# LB_BIT_1IN_3OUT-XL-v03_1_1x.net
KiCad netlist of a schematic drawn in EAGLE
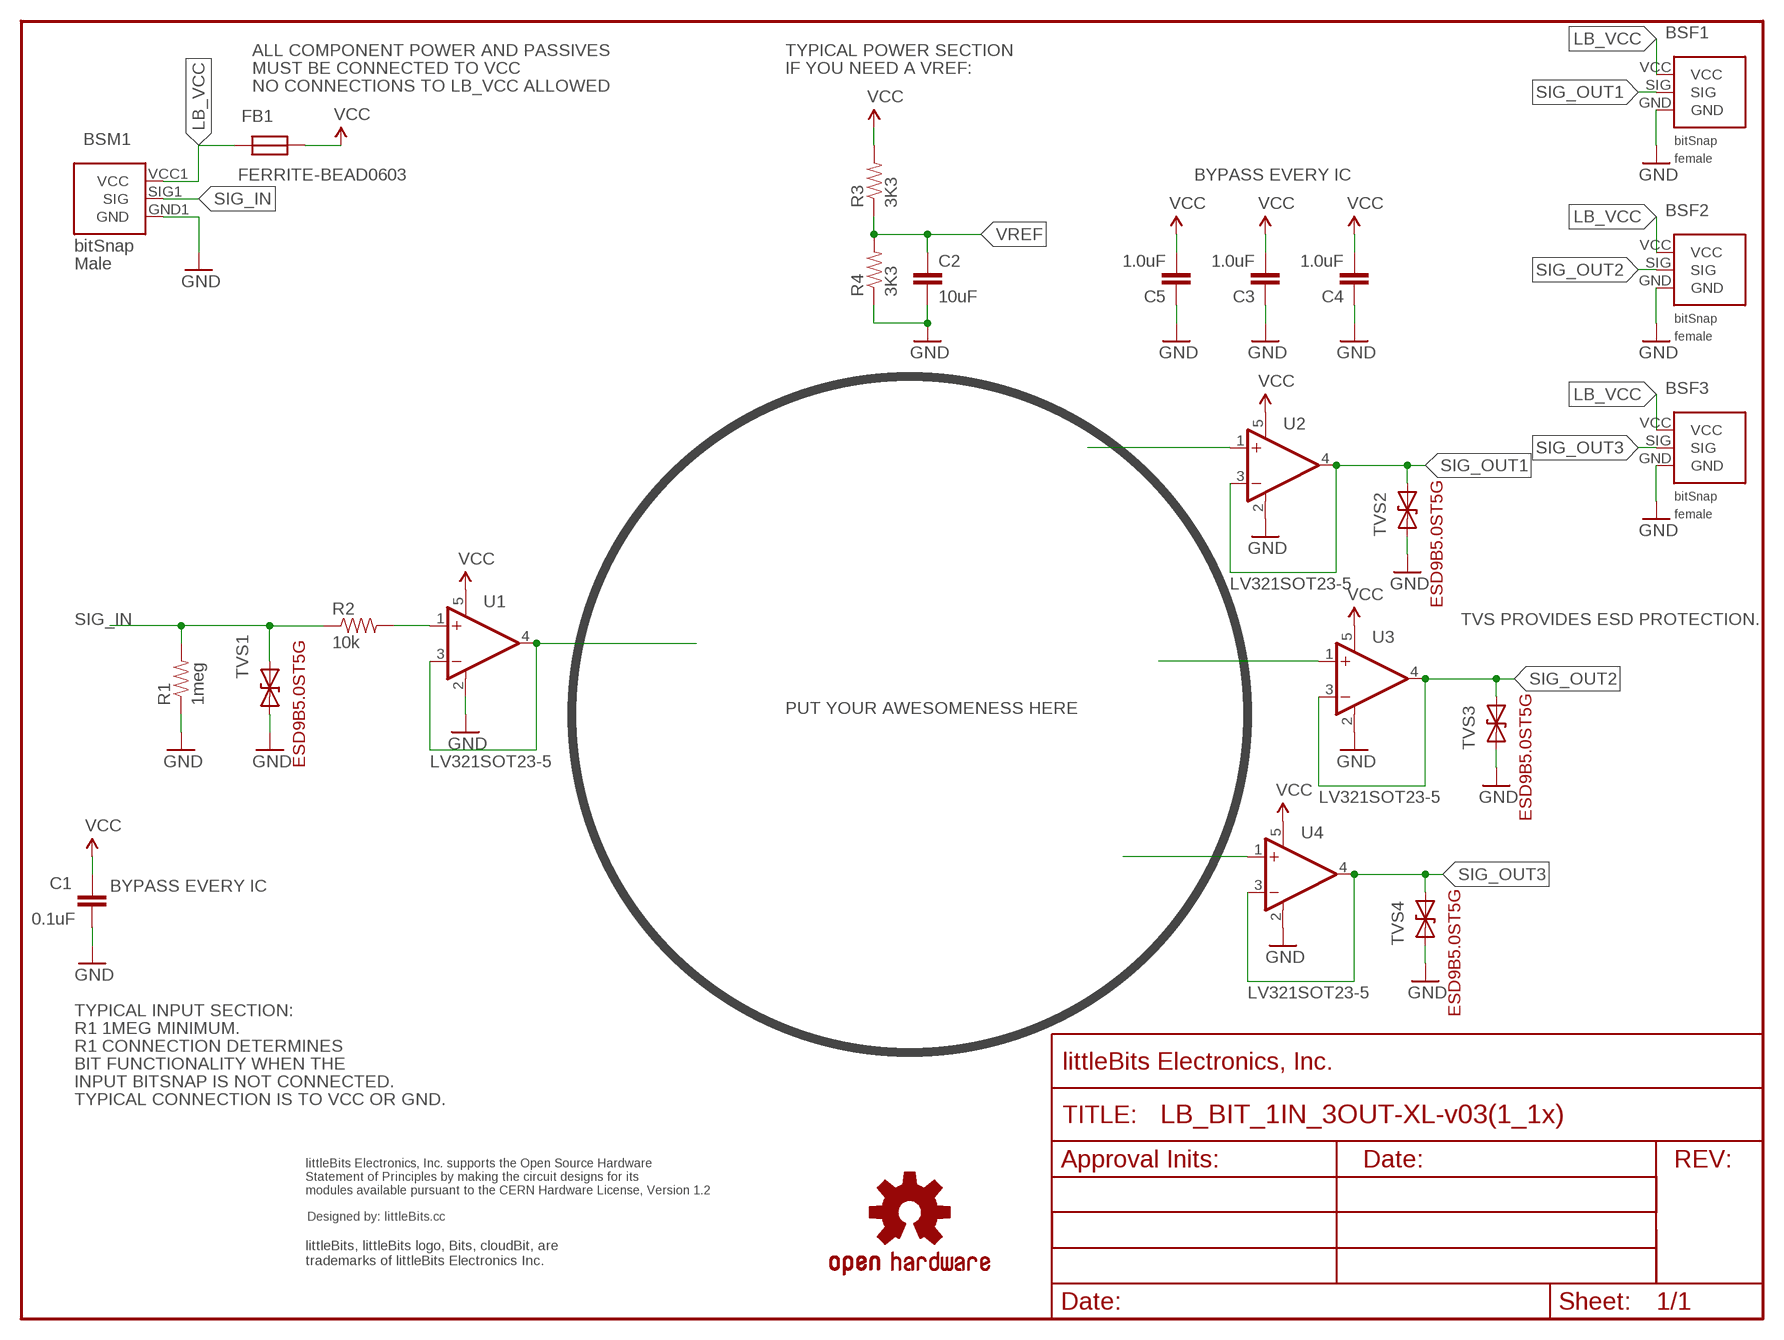
[diagram p0: schematic, sheet 1]

(export (version "E")
  (design (tool "Eeschema 10.0.6"))
  (components
    (comp (ref "BSF1")
      (value "BITSNAP_V03_FEMALE")
      (footprint "eagle-import:BITSNAP_V03_FEMALE")
      (libsource (lib "eagle-import") (part "BITSNAP_V03_FEMALE"))
    )
    (comp (ref "BSF2")
      (value "BITSNAP_V03_FEMALE")
      (footprint "eagle-import:BITSNAP_V03_FEMALE")
      (libsource (lib "eagle-import") (part "BITSNAP_V03_FEMALE"))
    )
    (comp (ref "BSF3")
      (value "BITSNAP_V03_FEMALE")
      (footprint "eagle-import:BITSNAP_V03_FEMALE")
      (libsource (lib "eagle-import") (part "BITSNAP_V03_FEMALE"))
    )
    (comp (ref "BSM1")
      (value "BITSNAP_V03_MALE")
      (footprint "eagle-import:BITSNAP_V03_MALE")
      (libsource (lib "eagle-import") (part "BITSNAP_V03_MALE"))
    )
    (comp (ref "C1")
      (value "0.1uF")
      (footprint "eagle-import:CAP-0603")
      (libsource (lib "eagle-import") (part "CAPCAP-0603"))
    )
    (comp (ref "C2")
      (value "10uF")
      (footprint "eagle-import:CAP-0603")
      (libsource (lib "eagle-import") (part "CAPCAP-0603"))
    )
    (comp (ref "C3")
      (value "1.0uF")
      (footprint "eagle-import:CAP-0603")
      (libsource (lib "eagle-import") (part "CAPCAP-0603"))
    )
    (comp (ref "C4")
      (value "1.0uF")
      (footprint "eagle-import:CAP-0603")
      (libsource (lib "eagle-import") (part "CAPCAP-0603"))
    )
    (comp (ref "C5")
      (value "1.0uF")
      (footprint "eagle-import:CAP-0603")
      (libsource (lib "eagle-import") (part "CAPCAP-0603"))
    )
    (comp (ref "FB1")
      (value "FERRITE-BEAD0603")
      (footprint "eagle-import:R0603")
      (libsource (lib "eagle-import") (part "FERRITE-BEAD0603"))
    )
    (comp (ref "FRAME1")
      (value "FRAME-LETTER")
      (footprint "eagle-import:FABDWG01-OHW")
      (libsource (lib "eagle-import") (part "FRAME-LETTER"))
    )
    (comp (ref "R1")
      (value "1meg")
      (footprint "eagle-import:RES-0603")
      (libsource (lib "eagle-import") (part "RESISTOR0603"))
    )
    (comp (ref "R2")
      (value "10k")
      (footprint "eagle-import:RES-0603")
      (libsource (lib "eagle-import") (part "RESISTOR0603"))
    )
    (comp (ref "R3")
      (value "3K3")
      (footprint "eagle-import:RES-0603")
      (libsource (lib "eagle-import") (part "RESISTOR0603"))
    )
    (comp (ref "R4")
      (value "3K3")
      (footprint "eagle-import:RES-0603")
      (libsource (lib "eagle-import") (part "RESISTOR0603"))
    )
    (comp (ref "TVS1")
      (value "DIODE-TVSSOD-923")
      (footprint "eagle-import:SOD-923")
      (fields (field (name "MPN") "ESD9B5.0ST5G"))
      (libsource (lib "eagle-import") (part "DIODE-TVSSOD-923"))
    )
    (comp (ref "TVS2")
      (value "DIODE-TVSSOD-923")
      (footprint "eagle-import:SOD-923")
      (fields (field (name "MPN") "ESD9B5.0ST5G"))
      (libsource (lib "eagle-import") (part "DIODE-TVSSOD-923"))
    )
    (comp (ref "TVS3")
      (value "DIODE-TVSSOD-923")
      (footprint "eagle-import:SOD-923")
      (fields (field (name "MPN") "ESD9B5.0ST5G"))
      (libsource (lib "eagle-import") (part "DIODE-TVSSOD-923"))
    )
    (comp (ref "TVS4")
      (value "DIODE-TVSSOD-923")
      (footprint "eagle-import:SOD-923")
      (fields (field (name "MPN") "ESD9B5.0ST5G"))
      (libsource (lib "eagle-import") (part "DIODE-TVSSOD-923"))
    )
    (comp (ref "U$1")
      (value "OSHWCREDIT")
      (footprint "eagle-import:OSHWCREDIT")
      (libsource (lib "eagle-import") (part "OSHWCREDIT"))
    )
    (comp (ref "U$6")
      (value "OSHW-LOGOL")
      (footprint "eagle-import:OSHW-LOGO-L")
      (libsource (lib "eagle-import") (part "OSHW-LOGOL"))
    )
    (comp (ref "U1")
      (value "LV321SOT23-5")
      (footprint "eagle-import:SOT23-5")
      (libsource (lib "eagle-import") (part "LV321SOT23-5"))
    )
    (comp (ref "U2")
      (value "LV321SOT23-5")
      (footprint "eagle-import:SOT23-5")
      (libsource (lib "eagle-import") (part "LV321SOT23-5"))
    )
    (comp (ref "U3")
      (value "LV321SOT23-5")
      (footprint "eagle-import:SOT23-5")
      (libsource (lib "eagle-import") (part "LV321SOT23-5"))
    )
    (comp (ref "U4")
      (value "LV321SOT23-5")
      (footprint "eagle-import:SOT23-5")
      (libsource (lib "eagle-import") (part "LV321SOT23-5"))
    )
  )
  (nets
    (net (code "1") (name "GND") (class "Default")
      (node (ref "BSF1") (pin "GND") (pinfunction "GND_GND") (pintype "bidirectional"))
      (node (ref "BSF2") (pin "GND") (pinfunction "GND_GND") (pintype "bidirectional"))
      (node (ref "BSF3") (pin "GND") (pinfunction "GND_GND") (pintype "bidirectional"))
      (node (ref "BSM1") (pin "GND1") (pinfunction "GND_GND1") (pintype "bidirectional"))
      (node (ref "C1") (pin "2") (pinfunction "2_2") (pintype "passive"))
      (node (ref "C2") (pin "2") (pinfunction "2_2") (pintype "passive"))
      (node (ref "C3") (pin "1") (pinfunction "1_1") (pintype "passive"))
      (node (ref "C4") (pin "1") (pinfunction "1_1") (pintype "passive"))
      (node (ref "C5") (pin "1") (pinfunction "1_1") (pintype "passive"))
      (node (ref "R1") (pin "1") (pinfunction "1_1") (pintype "passive"))
      (node (ref "R4") (pin "1") (pinfunction "1_1") (pintype "passive"))
      (node (ref "TVS1") (pin "1") (pinfunction "A_1") (pintype "passive"))
      (node (ref "TVS2") (pin "1") (pinfunction "A_1") (pintype "passive"))
      (node (ref "TVS3") (pin "1") (pinfunction "A_1") (pintype "passive"))
      (node (ref "TVS4") (pin "1") (pinfunction "A_1") (pintype "passive"))
      (node (ref "U1") (pin "2") (pinfunction "V-_2") (pintype "power_in"))
      (node (ref "U2") (pin "2") (pinfunction "V-_2") (pintype "power_in"))
      (node (ref "U3") (pin "2") (pinfunction "V-_2") (pintype "power_in"))
      (node (ref "U4") (pin "2") (pinfunction "V-_2") (pintype "power_in"))
    )
    (net (code "2") (name "LB_VCC") (class "Default")
      (node (ref "BSF1") (pin "VCC") (pinfunction "VCC_VCC") (pintype "bidirectional"))
      (node (ref "BSF2") (pin "VCC") (pinfunction "VCC_VCC") (pintype "bidirectional"))
      (node (ref "BSF3") (pin "VCC") (pinfunction "VCC_VCC") (pintype "bidirectional"))
      (node (ref "BSM1") (pin "VCC1") (pinfunction "VCC_VCC1") (pintype "bidirectional"))
      (node (ref "FB1") (pin "2") (pinfunction "P$2_2") (pintype "bidirectional"))
    )
    (net (code "3") (name "Net-(U1-+IN)") (class "Default")
      (node (ref "R2") (pin "2") (pinfunction "2_2") (pintype "passive"))
      (node (ref "U1") (pin "1") (pinfunction "+IN_1") (pintype "input"))
    )
    (net (code "4") (name "Net-(U1--IN)") (class "Default")
      (node (ref "U1") (pin "3") (pinfunction "-IN_3") (pintype "input"))
      (node (ref "U1") (pin "4") (pinfunction "OUT_4") (pintype "output"))
    )
    (net (code "5") (name "SIG_IN") (class "Default")
      (node (ref "BSM1") (pin "SIG1") (pinfunction "SIG_SIG1") (pintype "bidirectional"))
      (node (ref "R1") (pin "2") (pinfunction "2_2") (pintype "passive"))
      (node (ref "R2") (pin "1") (pinfunction "1_1") (pintype "passive"))
      (node (ref "TVS1") (pin "2") (pinfunction "C_2") (pintype "passive"))
    )
    (net (code "6") (name "SIG_OUT1") (class "Default")
      (node (ref "BSF1") (pin "SIG") (pinfunction "SIG_SIG") (pintype "bidirectional"))
      (node (ref "TVS2") (pin "2") (pinfunction "C_2") (pintype "passive"))
      (node (ref "U2") (pin "3") (pinfunction "-IN_3") (pintype "input"))
      (node (ref "U2") (pin "4") (pinfunction "OUT_4") (pintype "output"))
    )
    (net (code "7") (name "SIG_OUT2") (class "Default")
      (node (ref "BSF2") (pin "SIG") (pinfunction "SIG_SIG") (pintype "bidirectional"))
      (node (ref "TVS3") (pin "2") (pinfunction "C_2") (pintype "passive"))
      (node (ref "U3") (pin "3") (pinfunction "-IN_3") (pintype "input"))
      (node (ref "U3") (pin "4") (pinfunction "OUT_4") (pintype "output"))
    )
    (net (code "8") (name "SIG_OUT3") (class "Default")
      (node (ref "BSF3") (pin "SIG") (pinfunction "SIG_SIG") (pintype "bidirectional"))
      (node (ref "TVS4") (pin "2") (pinfunction "C_2") (pintype "passive"))
      (node (ref "U4") (pin "3") (pinfunction "-IN_3") (pintype "input"))
      (node (ref "U4") (pin "4") (pinfunction "OUT_4") (pintype "output"))
    )
    (net (code "9") (name "VCC") (class "Default")
      (node (ref "C1") (pin "1") (pinfunction "1_1") (pintype "passive"))
      (node (ref "C3") (pin "2") (pinfunction "2_2") (pintype "passive"))
      (node (ref "C4") (pin "2") (pinfunction "2_2") (pintype "passive"))
      (node (ref "C5") (pin "2") (pinfunction "2_2") (pintype "passive"))
      (node (ref "FB1") (pin "1") (pinfunction "P$1_1") (pintype "bidirectional"))
      (node (ref "R3") (pin "2") (pinfunction "2_2") (pintype "passive"))
      (node (ref "U1") (pin "5") (pinfunction "V+_5") (pintype "power_in"))
      (node (ref "U2") (pin "5") (pinfunction "V+_5") (pintype "power_in"))
      (node (ref "U3") (pin "5") (pinfunction "V+_5") (pintype "power_in"))
      (node (ref "U4") (pin "5") (pinfunction "V+_5") (pintype "power_in"))
    )
    (net (code "10") (name "VREF") (class "Default")
      (node (ref "C2") (pin "1") (pinfunction "1_1") (pintype "passive"))
      (node (ref "R3") (pin "1") (pinfunction "1_1") (pintype "passive"))
      (node (ref "R4") (pin "2") (pinfunction "2_2") (pintype "passive"))
    )
    (net (code "11") (name "unconnected-(U2-+IN-Pad1)") (class "Default")
      (node (ref "U2") (pin "1") (pinfunction "+IN_1") (pintype "input"))
    )
    (net (code "12") (name "unconnected-(U3-+IN-Pad1)") (class "Default")
      (node (ref "U3") (pin "1") (pinfunction "+IN_1") (pintype "input"))
    )
    (net (code "13") (name "unconnected-(U4-+IN-Pad1)") (class "Default")
      (node (ref "U4") (pin "1") (pinfunction "+IN_1") (pintype "input"))
    )
  )
)
